# schematics.net
KiCad netlist of a schematic drawn in Altium Designer
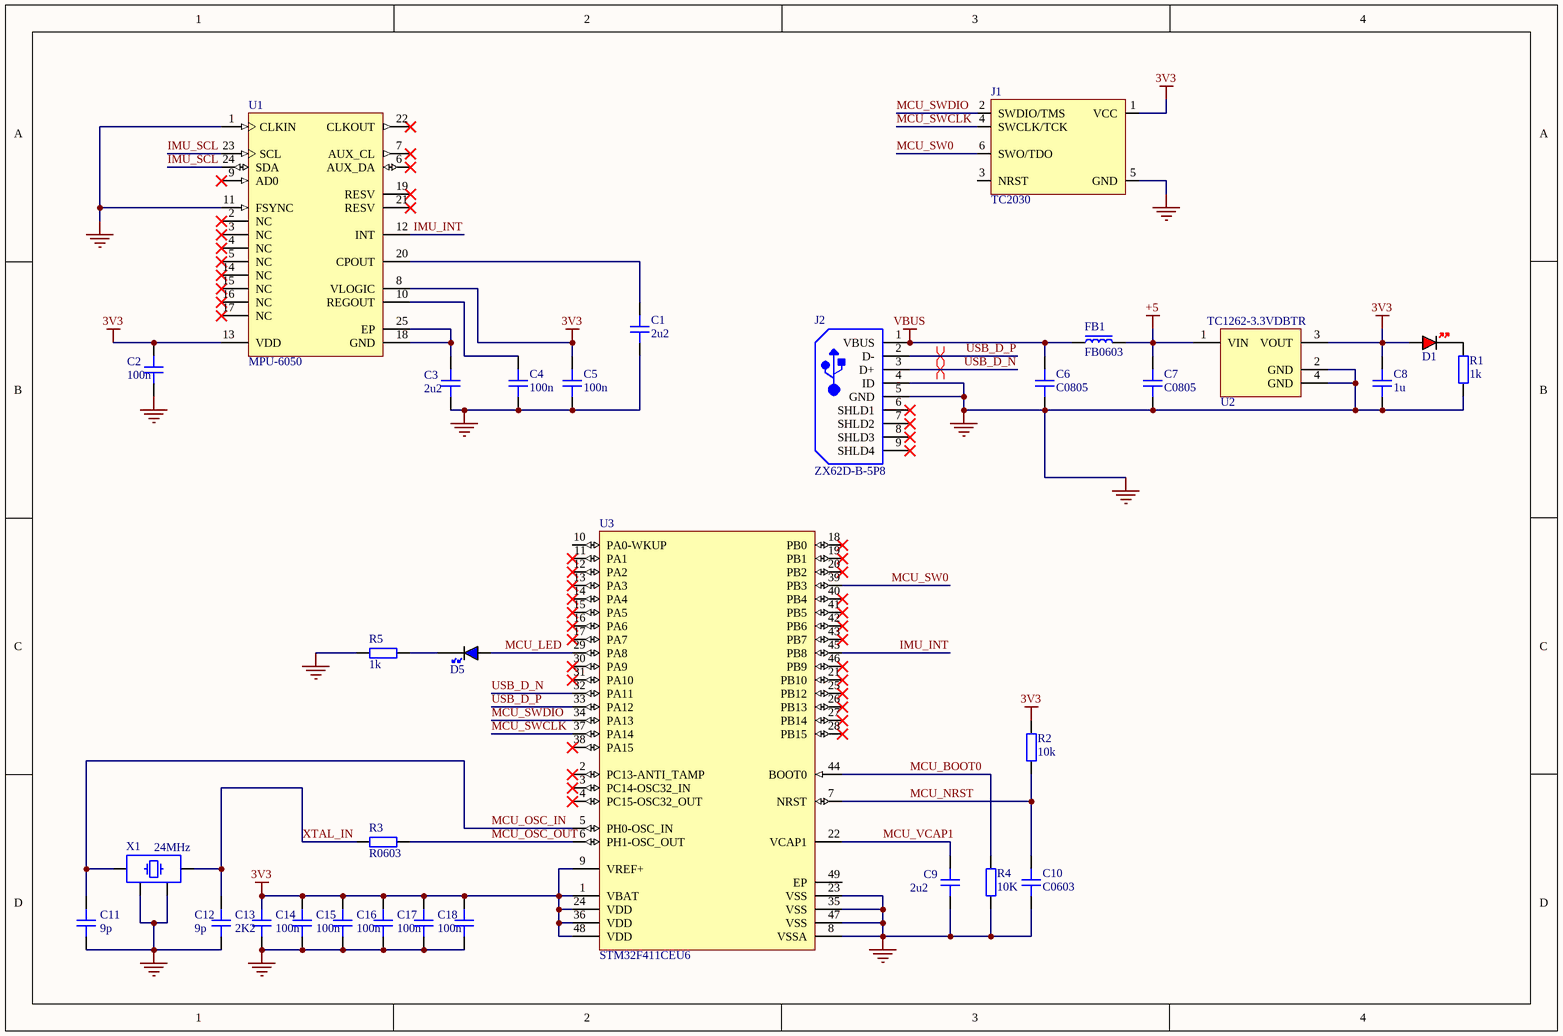
[diagram p0: schematics.SchDoc]

(export (version "E")
  (design (tool "Eeschema 10.0.6"))
  (components
    (comp (ref "C1")
      (value "2u2")
      (footprint "CAP_0603")
      (description "Capacitor SMD 0603")
      (libsource (lib "Schematic-Lib-PhilsLab") (part "CAP_0603"))
    )
    (comp (ref "C2")
      (value "100n")
      (footprint "CAP_0603")
      (description "Capacitor SMD 0603")
      (libsource (lib "Schematic-Lib-PhilsLab") (part "CAP_0603"))
    )
    (comp (ref "C3")
      (value "2u2")
      (footprint "CAP_0603")
      (description "Capacitor SMD 0603")
      (libsource (lib "Schematic-Lib-PhilsLab") (part "CAP_0603"))
    )
    (comp (ref "C4")
      (value "100n")
      (footprint "CAP_0603")
      (description "Capacitor SMD 0603")
      (libsource (lib "Schematic-Lib-PhilsLab") (part "CAP_0603"))
    )
    (comp (ref "C5")
      (value "100n")
      (footprint "CAP_0603")
      (description "Capacitor SMD 0603")
      (libsource (lib "Schematic-Lib-PhilsLab") (part "CAP_0603"))
    )
    (comp (ref "C6")
      (value "C0805")
      (footprint "CAP_0805")
      (description "Capacitor SMD 0805")
      (libsource (lib "Schematic-Lib-PhilsLab") (part "CAP_0805"))
    )
    (comp (ref "C7")
      (value "C0805")
      (footprint "CAP_0805")
      (description "Capacitor SMD 0805")
      (libsource (lib "Schematic-Lib-PhilsLab") (part "CAP_0805"))
    )
    (comp (ref "C8")
      (value "1u")
      (footprint "CAP_0603")
      (description "Capacitor SMD 0603")
      (libsource (lib "Schematic-Lib-PhilsLab") (part "CAP_0603"))
    )
    (comp (ref "C9")
      (value "2u2")
      (footprint "CAP_0603")
      (description "Capacitor SMD 0603")
      (libsource (lib "Schematic-Lib-PhilsLab") (part "CAP_0603"))
    )
    (comp (ref "C10")
      (value "C0603")
      (footprint "CAP_0603")
      (description "Capacitor SMD 0603")
      (libsource (lib "Schematic-Lib-PhilsLab") (part "CAP_0603"))
    )
    (comp (ref "C11")
      (value "9p")
      (footprint "CAP_0603")
      (description "Capacitor SMD 0603")
      (fields
        (field (name "MANUFACTURER") "Seiko Epson")
        (field (name "MANUFACTURER PART NUMBER") "X1E0000210127")
      )
      (libsource (lib "Schematic-Lib-PhilsLab") (part "CAP_0603"))
    )
    (comp (ref "C12")
      (value "9p")
      (footprint "CAP_0603")
      (description "Capacitor SMD 0603")
      (fields
        (field (name "MANUFACTURER") "Seiko Epson")
        (field (name "MANUFACTURER PART NUMBER") "X1E0000210127")
      )
      (libsource (lib "Schematic-Lib-PhilsLab") (part "CAP_0603"))
    )
    (comp (ref "C13")
      (value "2K2")
      (footprint "CAP_0603")
      (description "Capacitor SMD 0603")
      (libsource (lib "Schematic-Lib-PhilsLab") (part "CAP_0603"))
    )
    (comp (ref "C14")
      (value "100n")
      (footprint "CAP_0603")
      (description "Capacitor SMD 0603")
      (libsource (lib "Schematic-Lib-PhilsLab") (part "CAP_0603"))
    )
    (comp (ref "C15")
      (value "100n")
      (footprint "CAP_0603")
      (description "Capacitor SMD 0603")
      (libsource (lib "Schematic-Lib-PhilsLab") (part "CAP_0603"))
    )
    (comp (ref "C16")
      (value "100n")
      (footprint "CAP_0603")
      (description "Capacitor SMD 0603")
      (libsource (lib "Schematic-Lib-PhilsLab") (part "CAP_0603"))
    )
    (comp (ref "C17")
      (value "100n")
      (footprint "CAP_0603")
      (description "Capacitor SMD 0603")
      (libsource (lib "Schematic-Lib-PhilsLab") (part "CAP_0603"))
    )
    (comp (ref "C18")
      (value "100n")
      (footprint "CAP_0603")
      (description "Capacitor SMD 0603")
      (libsource (lib "Schematic-Lib-PhilsLab") (part "CAP_0603"))
    )
    (comp (ref "D1")
      (value "RED")
      (footprint "LED_0402_RED")
      (description "LED 0402 RED SMD")
      (libsource (lib "Schematic-Lib-PhilsLab") (part "LED_0402_RED"))
    )
    (comp (ref "D5")
      (value "BLUE")
      (footprint "LED_0402_BLUE")
      (description "LED 0402 BLUE SMD")
      (libsource (lib "Schematic-Lib-PhilsLab") (part "LED_0402_BLUE"))
    )
    (comp (ref "FB1")
      (value "FB0603")
      (footprint "FB_0603")
      (description "Ferrite Bead SMD 0603")
      (libsource (lib "Schematic-Lib-PhilsLab") (part "FB_0603"))
    )
    (comp (ref "J1")
      (value "TC2030")
      (footprint "TC2030-FP")
      (description "Tag-Connect No-Solder SWD Debug Connector DO NOT PLACE")
      (fields (field (name "MANUFACTURER") "Tag-Connect"))
      (libsource (lib "Schematic-Lib-PhilsLab") (part "TC2030"))
    )
    (comp (ref "J2")
      (value "ZX62D-B-5P8")
      (footprint "HIRO-ZX62D-B-5P8_V")
      (fields (field (name "MANUFACTURER") "Hirose Electric"))
      (libsource (lib "Abdel Manan Abdel Rahman") (part "USB-5-4SHLD"))
    )
    (comp (ref "R1")
      (value "1k")
      (footprint "RES_0603")
      (description "Resistor SMD 0603")
      (libsource (lib "Schematic-Lib-PhilsLab") (part "RES_0603"))
    )
    (comp (ref "R2")
      (value "10k")
      (footprint "RES_0603")
      (description "Resistor SMD 0603")
      (libsource (lib "Schematic-Lib-PhilsLab") (part "RES_0603"))
    )
    (comp (ref "R3")
      (value "R0603")
      (footprint "RES_0603")
      (description "Resistor SMD 0603")
      (libsource (lib "Schematic-Lib-PhilsLab") (part "RES_0603"))
    )
    (comp (ref "R4")
      (value "10K")
      (footprint "RES_0603")
      (description "Resistor SMD 0603")
      (libsource (lib "Schematic-Lib-PhilsLab") (part "RES_0603"))
    )
    (comp (ref "R5")
      (value "1k")
      (footprint "RES_0603")
      (description "Resistor SMD 0603")
      (libsource (lib "Schematic-Lib-PhilsLab") (part "RES_0603"))
    )
    (comp (ref "U1")
      (value "MPU-6050")
      (footprint "IS-QFN-24_V")
      (fields (field (name "MANUFACTURER") "InvenSense"))
      (libsource (lib "Altium Content Vault") (part "IS-MPU-6050-QFN-24"))
    )
    (comp (ref "U2")
      (value "TC1262-3.3VDBTR")
      (footprint "SOT-223-DB3_N")
      (description "500mA Fixed Output CMOS LDO, 3-Pin SOT-223, Extended Temperature, Tape and Reel")
      (libsource (lib "Altium Content Vault") (part "PM-LINEREG-TC1262-IL4"))
    )
    (comp (ref "U3")
      (value "STM32F411CEU6")
      (footprint "STM-UFQFPN48_L")
      (libsource (lib "Altium Content Vault") (part "MC-ARM-STM32F411-UFQFPN48"))
    )
    (comp (ref "X1")
      (value "24MHz")
      (footprint "XTAL_3225")
      (description "Crystal SMD 24MHz 10PPM 7pF 3225")
      (fields
        (field (name "MANUFACTURER") "Epson")
        (field (name "MANUFACTURER PART NUMBER") "TSX-3225 24.0000MF15X-AC")
      )
      (libsource (lib "Schematic-Lib-PhilsLab") (part "TSX-3225_24.0000MF15X-AC"))
    )
  )
  (nets
    (net (code "1") (name "+5") (class "Default")
      (node (ref "C7") (pin "2") (pinfunction "2_2") (pintype "passive"))
      (node (ref "FB1") (pin "2") (pinfunction "2_2") (pintype "passive"))
      (node (ref "U2") (pin "1") (pinfunction "VIN_1") (pintype "power_in"))
    )
    (net (code "2") (name "/IMU_INT") (class "Default")
      (node (ref "U1") (pin "12") (pinfunction "INT_12") (pintype "open_collector"))
      (node (ref "U3") (pin "45") (pinfunction "PB8_45") (pintype "bidirectional"))
    )
    (net (code "3") (name "/IMU_SCL") (class "Default")
      (node (ref "U1") (pin "23") (pinfunction "SCL_23") (pintype "input"))
      (node (ref "U1") (pin "24") (pinfunction "SDA_24") (pintype "bidirectional"))
    )
    (net (code "4") (name "/MCU_BOOT0") (class "Default")
      (node (ref "R4") (pin "1") (pinfunction "1_1") (pintype "passive"))
      (node (ref "U3") (pin "44") (pinfunction "BOOT0_44") (pintype "input"))
    )
    (net (code "5") (name "/MCU_LED") (class "Default")
      (node (ref "D5") (pin "A") (pinfunction "A_A") (pintype "passive"))
      (node (ref "U3") (pin "29") (pinfunction "PA8_29") (pintype "bidirectional"))
    )
    (net (code "6") (name "/MCU_NRST") (class "Default")
      (node (ref "C10") (pin "2") (pinfunction "2_2") (pintype "passive"))
      (node (ref "R2") (pin "2") (pinfunction "2_2") (pintype "passive"))
      (node (ref "U3") (pin "7") (pinfunction "NRST_7") (pintype "bidirectional"))
    )
    (net (code "7") (name "/MCU_OSC_IN") (class "Default")
      (node (ref "C11") (pin "2") (pinfunction "2_2") (pintype "passive"))
      (node (ref "U3") (pin "5") (pinfunction "PH0-OSC_IN_5") (pintype "bidirectional"))
      (node (ref "X1") (pin "1") (pinfunction "1_1") (pintype "passive"))
    )
    (net (code "8") (name "/MCU_OSC_OUT") (class "Default")
      (node (ref "R3") (pin "2") (pinfunction "2_2") (pintype "passive"))
      (node (ref "U3") (pin "6") (pinfunction "PH1-OSC_OUT_6") (pintype "bidirectional"))
    )
    (net (code "9") (name "/MCU_SW0") (class "Default")
      (node (ref "J1") (pin "6") (pinfunction "SWO/TDO_6") (pintype "passive"))
      (node (ref "U3") (pin "39") (pinfunction "PB3_39") (pintype "bidirectional"))
    )
    (net (code "10") (name "/MCU_SWCLK") (class "Default")
      (node (ref "J1") (pin "4") (pinfunction "SWCLK/TCK_4") (pintype "passive"))
      (node (ref "U3") (pin "37") (pinfunction "PA14_37") (pintype "bidirectional"))
    )
    (net (code "11") (name "/MCU_SWDIO") (class "Default")
      (node (ref "J1") (pin "2") (pinfunction "SWDIO/TMS_2") (pintype "passive"))
      (node (ref "U3") (pin "34") (pinfunction "PA13_34") (pintype "bidirectional"))
    )
    (net (code "12") (name "/MCU_VCAP1") (class "Default")
      (node (ref "C9") (pin "2") (pinfunction "2_2") (pintype "passive"))
      (node (ref "U3") (pin "22") (pinfunction "VCAP1_22") (pintype "passive"))
    )
    (net (code "13") (name "/USB_D_N") (class "Default")
      (node (ref "J2") (pin "3") (pinfunction "D+_3") (pintype "passive"))
      (node (ref "U3") (pin "32") (pinfunction "PA11_32") (pintype "bidirectional"))
    )
    (net (code "14") (name "/USB_D_P") (class "Default")
      (node (ref "J2") (pin "2") (pinfunction "D-_2") (pintype "passive"))
      (node (ref "U3") (pin "33") (pinfunction "PA12_33") (pintype "bidirectional"))
    )
    (net (code "15") (name "/XTAL_IN") (class "Default")
      (node (ref "C12") (pin "2") (pinfunction "2_2") (pintype "passive"))
      (node (ref "R3") (pin "1") (pinfunction "1_1") (pintype "passive"))
      (node (ref "X1") (pin "3") (pinfunction "3_3") (pintype "passive"))
    )
    (net (code "16") (name "3V3") (class "Default")
      (node (ref "C13") (pin "2") (pinfunction "2_2") (pintype "passive"))
      (node (ref "C14") (pin "2") (pinfunction "2_2") (pintype "passive"))
      (node (ref "C15") (pin "2") (pinfunction "2_2") (pintype "passive"))
      (node (ref "C16") (pin "2") (pinfunction "2_2") (pintype "passive"))
      (node (ref "C17") (pin "2") (pinfunction "2_2") (pintype "passive"))
      (node (ref "C18") (pin "2") (pinfunction "2_2") (pintype "passive"))
      (node (ref "C2") (pin "2") (pinfunction "2_2") (pintype "passive"))
      (node (ref "C5") (pin "2") (pinfunction "2_2") (pintype "passive"))
      (node (ref "C8") (pin "2") (pinfunction "2_2") (pintype "passive"))
      (node (ref "D1") (pin "A") (pinfunction "A_A") (pintype "passive"))
      (node (ref "J1") (pin "1") (pinfunction "VCC_1") (pintype "passive"))
      (node (ref "R2") (pin "1") (pinfunction "1_1") (pintype "passive"))
      (node (ref "U1") (pin "13") (pinfunction "VDD_13") (pintype "power_in"))
      (node (ref "U1") (pin "8") (pinfunction "VLOGIC_8") (pintype "power_in"))
      (node (ref "U2") (pin "3") (pinfunction "VOUT_3") (pintype "power_in"))
      (node (ref "U3") (pin "1") (pinfunction "VBAT_1") (pintype "power_in"))
      (node (ref "U3") (pin "24") (pinfunction "VDD_24") (pintype "power_in"))
      (node (ref "U3") (pin "36") (pinfunction "VDD_36") (pintype "power_in"))
      (node (ref "U3") (pin "48") (pinfunction "VDD_48") (pintype "power_in"))
      (node (ref "U3") (pin "9") (pinfunction "VREF+_9") (pintype "power_in"))
    )
    (net (code "17") (name "GND") (class "Default")
      (node (ref "C1") (pin "2") (pinfunction "2_2") (pintype "passive"))
      (node (ref "C10") (pin "1") (pinfunction "1_1") (pintype "passive"))
      (node (ref "C11") (pin "1") (pinfunction "1_1") (pintype "passive"))
      (node (ref "C12") (pin "1") (pinfunction "1_1") (pintype "passive"))
      (node (ref "C13") (pin "1") (pinfunction "1_1") (pintype "passive"))
      (node (ref "C14") (pin "1") (pinfunction "1_1") (pintype "passive"))
      (node (ref "C15") (pin "1") (pinfunction "1_1") (pintype "passive"))
      (node (ref "C16") (pin "1") (pinfunction "1_1") (pintype "passive"))
      (node (ref "C17") (pin "1") (pinfunction "1_1") (pintype "passive"))
      (node (ref "C18") (pin "1") (pinfunction "1_1") (pintype "passive"))
      (node (ref "C2") (pin "1") (pinfunction "1_1") (pintype "passive"))
      (node (ref "C3") (pin "1") (pinfunction "1_1") (pintype "passive"))
      (node (ref "C4") (pin "1") (pinfunction "1_1") (pintype "passive"))
      (node (ref "C5") (pin "1") (pinfunction "1_1") (pintype "passive"))
      (node (ref "C6") (pin "1") (pinfunction "1_1") (pintype "passive"))
      (node (ref "C7") (pin "1") (pinfunction "1_1") (pintype "passive"))
      (node (ref "C8") (pin "1") (pinfunction "1_1") (pintype "passive"))
      (node (ref "C9") (pin "1") (pinfunction "1_1") (pintype "passive"))
      (node (ref "J1") (pin "5") (pinfunction "GND_5") (pintype "passive"))
      (node (ref "J2") (pin "4") (pinfunction "ID_4") (pintype "passive"))
      (node (ref "J2") (pin "5") (pinfunction "GND_5") (pintype "passive"))
      (node (ref "R1") (pin "1") (pinfunction "1_1") (pintype "passive"))
      (node (ref "R4") (pin "2") (pinfunction "2_2") (pintype "passive"))
      (node (ref "R5") (pin "2") (pinfunction "2_2") (pintype "passive"))
      (node (ref "U1") (pin "1") (pinfunction "CLKIN_1") (pintype "input"))
      (node (ref "U1") (pin "11") (pinfunction "FSYNC_11") (pintype "input"))
      (node (ref "U2") (pin "2") (pinfunction "GND_2") (pintype "power_in"))
      (node (ref "U2") (pin "4") (pinfunction "GND_4") (pintype "power_in"))
      (node (ref "U3") (pin "23") (pinfunction "VSS_23") (pintype "power_in"))
      (node (ref "U3") (pin "35") (pinfunction "VSS_35") (pintype "power_in"))
      (node (ref "U3") (pin "47") (pinfunction "VSS_47") (pintype "power_in"))
      (node (ref "U3") (pin "8") (pinfunction "VSSA_8") (pintype "power_in"))
      (node (ref "X1") (pin "2") (pinfunction "2_2") (pintype "passive"))
      (node (ref "X1") (pin "4") (pinfunction "4_4") (pintype "passive"))
    )
    (net (code "18") (name "Net-(D1-PadK)") (class "Default")
      (node (ref "D1") (pin "K") (pinfunction "K_K") (pintype "passive"))
      (node (ref "R1") (pin "2") (pinfunction "2_2") (pintype "passive"))
    )
    (net (code "19") (name "Net-(D5-PadK)") (class "Default")
      (node (ref "D5") (pin "K") (pinfunction "K_K") (pintype "passive"))
      (node (ref "R5") (pin "1") (pinfunction "1_1") (pintype "passive"))
    )
    (net (code "20") (name "Net-(U1-CPOUT)") (class "Default")
      (node (ref "C1") (pin "1") (pinfunction "1_1") (pintype "passive"))
      (node (ref "U1") (pin "20") (pinfunction "CPOUT_20") (pintype "passive"))
    )
    (net (code "21") (name "Net-(U1-EP)") (class "Default")
      (node (ref "C3") (pin "2") (pinfunction "2_2") (pintype "passive"))
      (node (ref "U1") (pin "18") (pinfunction "GND_18") (pintype "power_in"))
      (node (ref "U1") (pin "25") (pinfunction "EP_25") (pintype "power_in"))
    )
    (net (code "22") (name "Net-(U1-REGOUT)") (class "Default")
      (node (ref "C4") (pin "2") (pinfunction "2_2") (pintype "passive"))
      (node (ref "U1") (pin "10") (pinfunction "REGOUT_10") (pintype "passive"))
    )
    (net (code "23") (name "VBUS") (class "Default")
      (node (ref "C6") (pin "2") (pinfunction "2_2") (pintype "passive"))
      (node (ref "FB1") (pin "1") (pinfunction "1_1") (pintype "passive"))
      (node (ref "J2") (pin "1") (pinfunction "VBUS_1") (pintype "passive"))
    )
    (net (code "24") (name "unconnected-(J1-NRST-Pad3)") (class "Default")
      (node (ref "J1") (pin "3") (pinfunction "NRST_3") (pintype "passive"))
    )
    (net (code "25") (name "unconnected-(J2-SHLD1-Pad6)") (class "Default")
      (node (ref "J2") (pin "6") (pinfunction "SHLD1_6") (pintype "passive+no_connect"))
    )
    (net (code "26") (name "unconnected-(J2-SHLD2-Pad7)") (class "Default")
      (node (ref "J2") (pin "7") (pinfunction "SHLD2_7") (pintype "passive+no_connect"))
    )
    (net (code "27") (name "unconnected-(J2-SHLD3-Pad8)") (class "Default")
      (node (ref "J2") (pin "8") (pinfunction "SHLD3_8") (pintype "passive+no_connect"))
    )
    (net (code "28") (name "unconnected-(J2-SHLD4-Pad9)") (class "Default")
      (node (ref "J2") (pin "9") (pinfunction "SHLD4_9") (pintype "passive+no_connect"))
    )
    (net (code "29") (name "unconnected-(U1-AD0-Pad9)") (class "Default")
      (node (ref "U1") (pin "9") (pinfunction "AD0_9") (pintype "input+no_connect"))
    )
    (net (code "30") (name "unconnected-(U1-AUX_CL-Pad7)") (class "Default")
      (node (ref "U1") (pin "7") (pinfunction "AUX_CL_7") (pintype "output+no_connect"))
    )
    (net (code "31") (name "unconnected-(U1-AUX_DA-Pad6)") (class "Default")
      (node (ref "U1") (pin "6") (pinfunction "AUX_DA_6") (pintype "bidirectional+no_connect"))
    )
    (net (code "32") (name "unconnected-(U1-CLKOUT-Pad22)") (class "Default")
      (node (ref "U1") (pin "22") (pinfunction "CLKOUT_22") (pintype "output+no_connect"))
    )
    (net (code "33") (name "unconnected-(U1-NC-Pad2)") (class "Default")
      (node (ref "U1") (pin "2") (pinfunction "NC_2") (pintype "passive+no_connect"))
    )
    (net (code "34") (name "unconnected-(U1-NC-Pad3)") (class "Default")
      (node (ref "U1") (pin "3") (pinfunction "NC_3") (pintype "passive+no_connect"))
    )
    (net (code "35") (name "unconnected-(U1-NC-Pad4)") (class "Default")
      (node (ref "U1") (pin "4") (pinfunction "NC_4") (pintype "passive+no_connect"))
    )
    (net (code "36") (name "unconnected-(U1-NC-Pad5)") (class "Default")
      (node (ref "U1") (pin "5") (pinfunction "NC_5") (pintype "passive+no_connect"))
    )
    (net (code "37") (name "unconnected-(U1-NC-Pad14)") (class "Default")
      (node (ref "U1") (pin "14") (pinfunction "NC_14") (pintype "passive+no_connect"))
    )
    (net (code "38") (name "unconnected-(U1-NC-Pad15)") (class "Default")
      (node (ref "U1") (pin "15") (pinfunction "NC_15") (pintype "passive+no_connect"))
    )
    (net (code "39") (name "unconnected-(U1-NC-Pad16)") (class "Default")
      (node (ref "U1") (pin "16") (pinfunction "NC_16") (pintype "passive+no_connect"))
    )
    (net (code "40") (name "unconnected-(U1-NC-Pad17)") (class "Default")
      (node (ref "U1") (pin "17") (pinfunction "NC_17") (pintype "passive+no_connect"))
    )
    (net (code "41") (name "unconnected-(U1-RESV-Pad19)") (class "Default")
      (node (ref "U1") (pin "19") (pinfunction "RESV_19") (pintype "passive+no_connect"))
    )
    (net (code "42") (name "unconnected-(U1-RESV-Pad21)") (class "Default")
      (node (ref "U1") (pin "21") (pinfunction "RESV_21") (pintype "passive+no_connect"))
    )
    (net (code "43") (name "unconnected-(U3-EP-Pad49)") (class "Default")
      (node (ref "U3") (pin "49") (pinfunction "EP_49") (pintype "power_in"))
    )
    (net (code "44") (name "unconnected-(U3-PA0-WKUP-Pad10)") (class "Default")
      (node (ref "U3") (pin "10") (pinfunction "PA0-WKUP_10") (pintype "bidirectional"))
    )
    (net (code "45") (name "unconnected-(U3-PA1-Pad11)") (class "Default")
      (node (ref "U3") (pin "11") (pinfunction "PA1_11") (pintype "bidirectional+no_connect"))
    )
    (net (code "46") (name "unconnected-(U3-PA2-Pad12)") (class "Default")
      (node (ref "U3") (pin "12") (pinfunction "PA2_12") (pintype "bidirectional+no_connect"))
    )
    (net (code "47") (name "unconnected-(U3-PA3-Pad13)") (class "Default")
      (node (ref "U3") (pin "13") (pinfunction "PA3_13") (pintype "bidirectional+no_connect"))
    )
    (net (code "48") (name "unconnected-(U3-PA4-Pad14)") (class "Default")
      (node (ref "U3") (pin "14") (pinfunction "PA4_14") (pintype "bidirectional+no_connect"))
    )
    (net (code "49") (name "unconnected-(U3-PA5-Pad15)") (class "Default")
      (node (ref "U3") (pin "15") (pinfunction "PA5_15") (pintype "bidirectional+no_connect"))
    )
    (net (code "50") (name "unconnected-(U3-PA6-Pad16)") (class "Default")
      (node (ref "U3") (pin "16") (pinfunction "PA6_16") (pintype "bidirectional+no_connect"))
    )
    (net (code "51") (name "unconnected-(U3-PA7-Pad17)") (class "Default")
      (node (ref "U3") (pin "17") (pinfunction "PA7_17") (pintype "bidirectional+no_connect"))
    )
    (net (code "52") (name "unconnected-(U3-PA9-Pad30)") (class "Default")
      (node (ref "U3") (pin "30") (pinfunction "PA9_30") (pintype "bidirectional+no_connect"))
    )
    (net (code "53") (name "unconnected-(U3-PA10-Pad31)") (class "Default")
      (node (ref "U3") (pin "31") (pinfunction "PA10_31") (pintype "bidirectional+no_connect"))
    )
    (net (code "54") (name "unconnected-(U3-PA15-Pad38)") (class "Default")
      (node (ref "U3") (pin "38") (pinfunction "PA15_38") (pintype "bidirectional+no_connect"))
    )
    (net (code "55") (name "unconnected-(U3-PB0-Pad18)") (class "Default")
      (node (ref "U3") (pin "18") (pinfunction "PB0_18") (pintype "bidirectional+no_connect"))
    )
    (net (code "56") (name "unconnected-(U3-PB1-Pad19)") (class "Default")
      (node (ref "U3") (pin "19") (pinfunction "PB1_19") (pintype "bidirectional+no_connect"))
    )
    (net (code "57") (name "unconnected-(U3-PB2-Pad20)") (class "Default")
      (node (ref "U3") (pin "20") (pinfunction "PB2_20") (pintype "bidirectional+no_connect"))
    )
    (net (code "58") (name "unconnected-(U3-PB4-Pad40)") (class "Default")
      (node (ref "U3") (pin "40") (pinfunction "PB4_40") (pintype "bidirectional+no_connect"))
    )
    (net (code "59") (name "unconnected-(U3-PB5-Pad41)") (class "Default")
      (node (ref "U3") (pin "41") (pinfunction "PB5_41") (pintype "bidirectional+no_connect"))
    )
    (net (code "60") (name "unconnected-(U3-PB6-Pad42)") (class "Default")
      (node (ref "U3") (pin "42") (pinfunction "PB6_42") (pintype "bidirectional+no_connect"))
    )
    (net (code "61") (name "unconnected-(U3-PB7-Pad43)") (class "Default")
      (node (ref "U3") (pin "43") (pinfunction "PB7_43") (pintype "bidirectional+no_connect"))
    )
    (net (code "62") (name "unconnected-(U3-PB9-Pad46)") (class "Default")
      (node (ref "U3") (pin "46") (pinfunction "PB9_46") (pintype "bidirectional+no_connect"))
    )
    (net (code "63") (name "unconnected-(U3-PB10-Pad21)") (class "Default")
      (node (ref "U3") (pin "21") (pinfunction "PB10_21") (pintype "bidirectional+no_connect"))
    )
    (net (code "64") (name "unconnected-(U3-PB12-Pad25)") (class "Default")
      (node (ref "U3") (pin "25") (pinfunction "PB12_25") (pintype "bidirectional+no_connect"))
    )
    (net (code "65") (name "unconnected-(U3-PB13-Pad26)") (class "Default")
      (node (ref "U3") (pin "26") (pinfunction "PB13_26") (pintype "bidirectional+no_connect"))
    )
    (net (code "66") (name "unconnected-(U3-PB14-Pad27)") (class "Default")
      (node (ref "U3") (pin "27") (pinfunction "PB14_27") (pintype "bidirectional+no_connect"))
    )
    (net (code "67") (name "unconnected-(U3-PB15-Pad28)") (class "Default")
      (node (ref "U3") (pin "28") (pinfunction "PB15_28") (pintype "bidirectional+no_connect"))
    )
    (net (code "68") (name "unconnected-(U3-PC13-ANTI_TAMP-Pad2)") (class "Default")
      (node (ref "U3") (pin "2") (pinfunction "PC13-ANTI_TAMP_2") (pintype "bidirectional+no_connect"))
    )
    (net (code "69") (name "unconnected-(U3-PC14-OSC32_IN-Pad3)") (class "Default")
      (node (ref "U3") (pin "3") (pinfunction "PC14-OSC32_IN_3") (pintype "bidirectional+no_connect"))
    )
    (net (code "70") (name "unconnected-(U3-PC15-OSC32_OUT-Pad4)") (class "Default")
      (node (ref "U3") (pin "4") (pinfunction "PC15-OSC32_OUT_4") (pintype "bidirectional+no_connect"))
    )
  )
)
